# Top_General.net
KiCad netlist of a schematic drawn in EAGLE
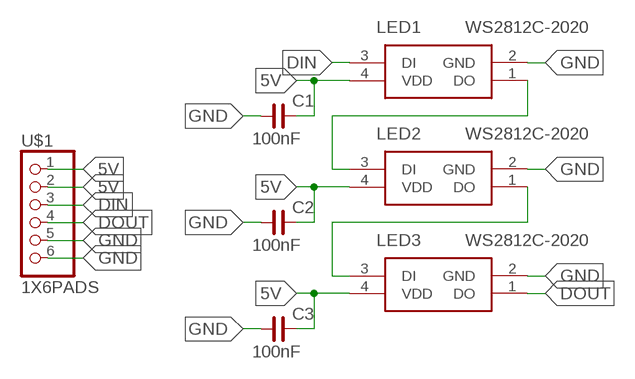
[diagram p0: schematic, sheet 1]

(export (version "E")
  (design (tool "Eeschema 10.0.6"))
  (components
    (comp (ref "C1")
      (value "100nF")
      (footprint "eagle-import:C0402")
      (libsource (lib "eagle-import") (part "C_0402"))
    )
    (comp (ref "C2")
      (value "100nF")
      (footprint "eagle-import:C0402")
      (libsource (lib "eagle-import") (part "C_0402"))
    )
    (comp (ref "C3")
      (value "100nF")
      (footprint "eagle-import:C0402")
      (libsource (lib "eagle-import") (part "C_0402"))
    )
    (comp (ref "LED1")
      (value "WS2812C-2020")
      (footprint "eagle-import:WS2812C2020")
      (libsource (lib "eagle-import") (part "WS2812C-2020"))
    )
    (comp (ref "LED2")
      (value "WS2812C-2020")
      (footprint "eagle-import:WS2812C2020")
      (libsource (lib "eagle-import") (part "WS2812C-2020"))
    )
    (comp (ref "LED3")
      (value "WS2812C-2020")
      (footprint "eagle-import:WS2812C2020")
      (libsource (lib "eagle-import") (part "WS2812C-2020"))
    )
    (comp (ref "U$1")
      (value "1X6PADS")
      (footprint "eagle-import:1X6PADS")
      (libsource (lib "eagle-import") (part "1X6PADS"))
    )
  )
  (nets
    (net (code "1") (name "5V") (class "Default")
      (node (ref "C1") (pin "2") (pinfunction "2_2") (pintype "passive"))
      (node (ref "C2") (pin "2") (pinfunction "2_2") (pintype "passive"))
      (node (ref "C3") (pin "2") (pinfunction "2_2") (pintype "passive"))
      (node (ref "LED1") (pin "4") (pinfunction "VDD_4") (pintype "bidirectional"))
      (node (ref "LED2") (pin "4") (pinfunction "VDD_4") (pintype "bidirectional"))
      (node (ref "LED3") (pin "4") (pinfunction "VDD_4") (pintype "bidirectional"))
      (node (ref "U$1") (pin "1") (pinfunction "1_1") (pintype "passive"))
      (node (ref "U$1") (pin "2") (pinfunction "2_2") (pintype "passive"))
    )
    (net (code "2") (name "DIN") (class "Default")
      (node (ref "LED1") (pin "3") (pinfunction "DI_3") (pintype "bidirectional"))
      (node (ref "U$1") (pin "3") (pinfunction "3_3") (pintype "passive"))
    )
    (net (code "3") (name "DOUT") (class "Default")
      (node (ref "LED3") (pin "1") (pinfunction "DO_1") (pintype "bidirectional"))
      (node (ref "U$1") (pin "4") (pinfunction "4_4") (pintype "passive"))
    )
    (net (code "4") (name "GND") (class "Default")
      (node (ref "C1") (pin "1") (pinfunction "1_1") (pintype "passive"))
      (node (ref "C2") (pin "1") (pinfunction "1_1") (pintype "passive"))
      (node (ref "C3") (pin "1") (pinfunction "1_1") (pintype "passive"))
      (node (ref "LED1") (pin "2") (pinfunction "GND_2") (pintype "bidirectional"))
      (node (ref "LED2") (pin "2") (pinfunction "GND_2") (pintype "bidirectional"))
      (node (ref "LED3") (pin "2") (pinfunction "GND_2") (pintype "bidirectional"))
      (node (ref "U$1") (pin "5") (pinfunction "5_5") (pintype "passive"))
      (node (ref "U$1") (pin "6") (pinfunction "6_6") (pintype "passive"))
    )
    (net (code "5") (name "Net-(LED1-DO)") (class "Default")
      (node (ref "LED1") (pin "1") (pinfunction "DO_1") (pintype "bidirectional"))
      (node (ref "LED2") (pin "3") (pinfunction "DI_3") (pintype "bidirectional"))
    )
    (net (code "6") (name "Net-(LED2-DO)") (class "Default")
      (node (ref "LED2") (pin "1") (pinfunction "DO_1") (pintype "bidirectional"))
      (node (ref "LED3") (pin "3") (pinfunction "DI_3") (pintype "bidirectional"))
    )
  )
)
